# STM32.net
KiCad netlist of a schematic drawn in Altium Designer
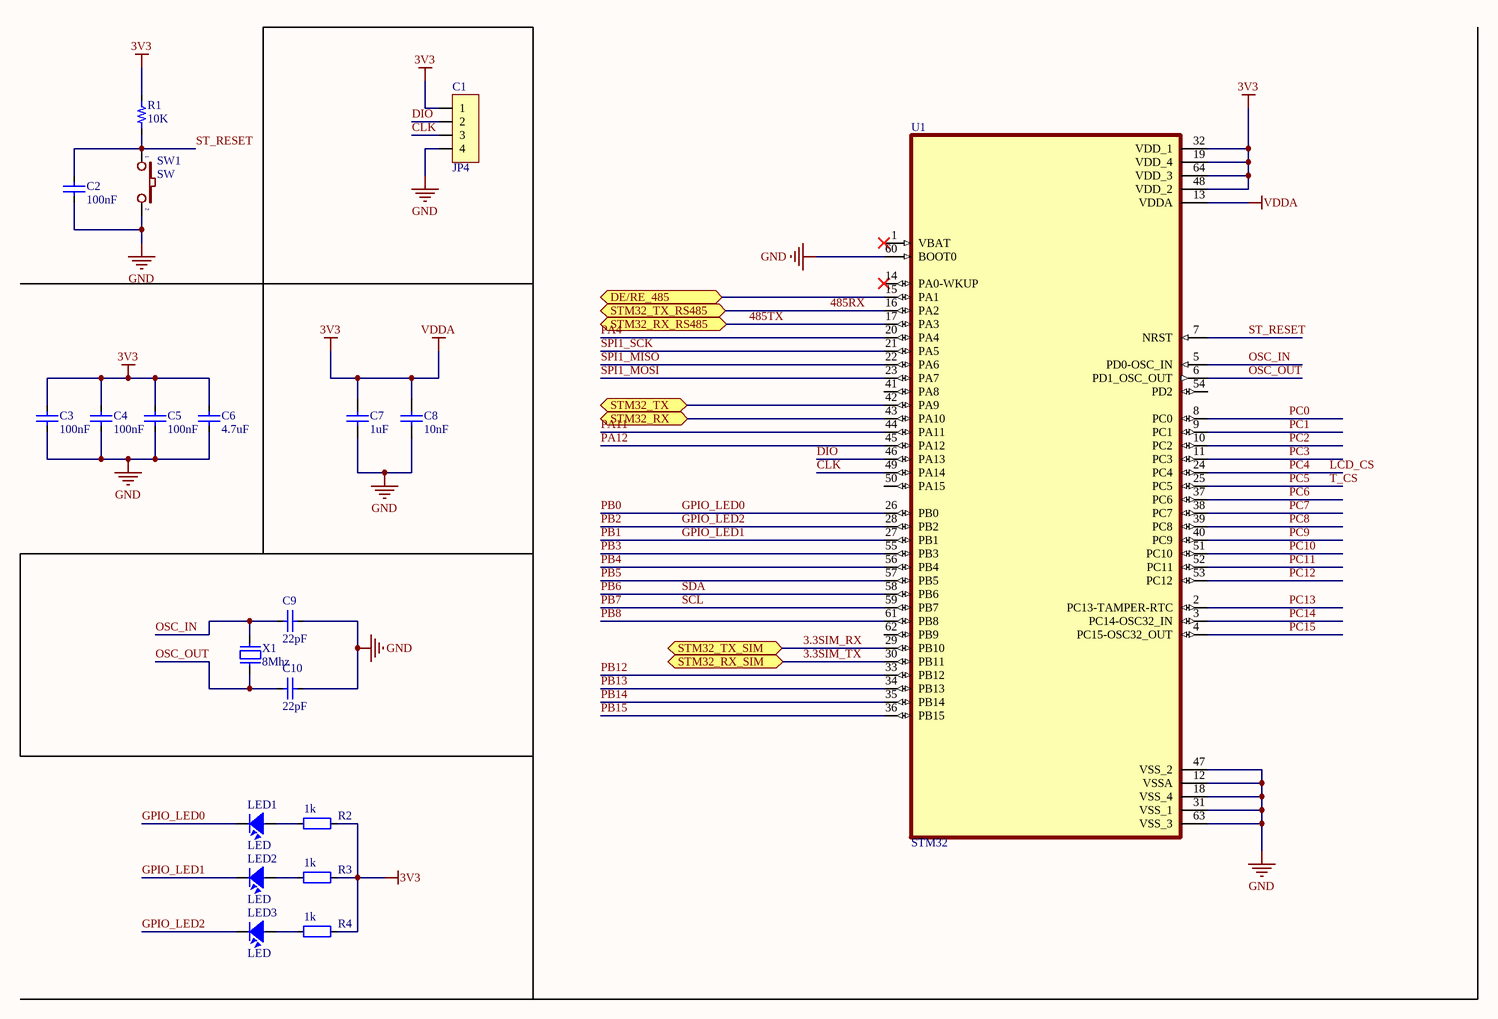
[diagram p0: STM32.SchDoc]

(export (version "E")
  (design (tool "Eeschema 10.0.6"))
  (components
    (comp (ref "C1")
      (value "JP4")
      (footprint "JP4-C1T")
      (description "WR-PHD 2.54 mm Angled Socket Header")
      (fields
        (field (name "MANUFACTURER") "Würth Elektronik eiSos GmbH")
        (field (name "PARTNO") "613004143121")
        (field (name "CREATED BY") "Karrer Zheng")
      )
      (libsource (lib "My-Library") (part "JP4"))
    )
    (comp (ref "C2")
      (value "100nF")
      (footprint "CAP_0805")
      (description "Capacitor")
      (fields (field (name "PUBLISHER") "Altium Limited"))
      (libsource (lib "My-Library") (part "CapSMD"))
    )
    (comp (ref "C3")
      (value "100nF")
      (footprint "CAP_0805")
      (description "Capacitor")
      (fields (field (name "PUBLISHER") "Altium Limited"))
      (libsource (lib "") (part "CapSMD_1"))
    )
    (comp (ref "C4")
      (value "100nF")
      (footprint "CAP_0805")
      (description "Capacitor")
      (fields (field (name "PUBLISHER") "Altium Limited"))
      (libsource (lib "") (part "CapSMD_1"))
    )
    (comp (ref "C5")
      (value "100nF")
      (footprint "CAP_0805")
      (description "Capacitor")
      (fields (field (name "PUBLISHER") "Altium Limited"))
      (libsource (lib "") (part "CapSMD_1"))
    )
    (comp (ref "C6")
      (value "4.7uF")
      (footprint "CAP_0805")
      (description "Capacitor")
      (fields (field (name "PUBLISHER") "Altium Limited"))
      (libsource (lib "") (part "CapSMD_1"))
    )
    (comp (ref "C7")
      (value "1uF")
      (footprint "CAP_0805")
      (description "Capacitor")
      (fields (field (name "PUBLISHER") "Altium Limited"))
      (libsource (lib "My Library") (part "CapSMD"))
    )
    (comp (ref "C8")
      (value "10nF")
      (footprint "CAP_0805")
      (description "Capacitor")
      (fields (field (name "PUBLISHER") "Altium Limited"))
      (libsource (lib "My Library") (part "CapSMD"))
    )
    (comp (ref "C9")
      (value "22pF")
      (footprint "CAP_0805")
      (description "Capacitor")
      (fields (field (name "PUBLISHER") "Altium Limited"))
      (libsource (lib "My-Library") (part "CapSMD"))
    )
    (comp (ref "C10")
      (value "22pF")
      (footprint "CAP_0805")
      (description "Capacitor")
      (fields (field (name "PUBLISHER") "Altium Limited"))
      (libsource (lib "My-Library") (part "CapSMD"))
    )
    (comp (ref "LED1")
      (value "LED")
      (footprint "LED-0805-Red")
      (description "LED Single colour Green and Red")
      (libsource (lib "My Library") (part "LED"))
    )
    (comp (ref "LED2")
      (value "LED")
      (footprint "LED-0805-Green")
      (description "LED Single colour Green and Red")
      (libsource (lib "My Library") (part "LED"))
    )
    (comp (ref "LED3")
      (value "LED")
      (footprint "LED-0805-Blue")
      (description "LED Single colour Green and Red")
      (libsource (lib "My Library") (part "LED"))
    )
    (comp (ref "R1")
      (value "10K")
      (footprint "RES-SMD-0101")
      (description "Resistor")
      (fields
        (field (name "MANUFACTURER") "Generic Components")
        (field (name "PUBLISHER") "Altium Hobart Technology Centre")
      )
      (libsource (lib "My-Library") (part "Resistor - SMD"))
    )
    (comp (ref "R2")
      (value "1k")
      (footprint "RES-SMD-0805")
      (description "Resistor")
      (fields
        (field (name "MANUFACTURER") "Generic Components")
        (field (name "PUBLISHER") "Altium Hobart Technology Centre")
      )
      (libsource (lib "My Library") (part "Resistor - SMD"))
    )
    (comp (ref "R3")
      (value "1k")
      (footprint "RES-SMD-0805")
      (description "Resistor")
      (fields
        (field (name "MANUFACTURER") "Generic Components")
        (field (name "PUBLISHER") "Altium Hobart Technology Centre")
      )
      (libsource (lib "My Library") (part "Resistor - SMD"))
    )
    (comp (ref "R4")
      (value "1k")
      (footprint "RES-SMD-0805")
      (description "Resistor")
      (fields
        (field (name "MANUFACTURER") "Generic Components")
        (field (name "PUBLISHER") "Altium Hobart Technology Centre")
      )
      (libsource (lib "My Library") (part "Resistor - SMD"))
    )
    (comp (ref "SW1")
      (value "SW")
      (footprint "SW2")
      (description "Switch button 2 pin")
      (libsource (lib "My-Library") (part "SW2"))
    )
    (comp (ref "U1")
      (value "STM32")
      (footprint "LQFP 64")
      (description "STM32 ARM-based 32-bit MCU 72MHz 256KB")
      (libsource (lib "Main") (part "STM32F103RCT6"))
    )
    (comp (ref "X1")
      (value "8Mhz")
      (footprint "XT2")
      (description "Crystal For all Crystal 2pin.")
      (libsource (lib "My-Library") (part "XT2"))
    )
  )
  (nets
    (net (code "1") (name "/3.3SIM_RX") (class "Default")
      (node (ref "U1") (pin "29") (pinfunction "PB10_29") (pintype "bidirectional"))
    )
    (net (code "2") (name "/3.3SIM_TX") (class "Default")
      (node (ref "U1") (pin "30") (pinfunction "PB11_30") (pintype "bidirectional"))
    )
    (net (code "3") (name "/485RX") (class "Default")
      (node (ref "U1") (pin "16") (pinfunction "PA2_16") (pintype "bidirectional"))
    )
    (net (code "4") (name "/485TX") (class "Default")
      (node (ref "U1") (pin "17") (pinfunction "PA3_17") (pintype "bidirectional"))
    )
    (net (code "5") (name "/CLK") (class "Default")
      (node (ref "C1") (pin "3") (pinfunction "3_3") (pintype "passive"))
      (node (ref "U1") (pin "49") (pinfunction "PA14_49") (pintype "bidirectional"))
    )
    (net (code "6") (name "/DE{slash}RE_485") (class "Default")
      (node (ref "U1") (pin "15") (pinfunction "PA1_15") (pintype "bidirectional"))
    )
    (net (code "7") (name "/DIO") (class "Default")
      (node (ref "C1") (pin "2") (pinfunction "2_2") (pintype "passive"))
      (node (ref "U1") (pin "46") (pinfunction "PA13_46") (pintype "bidirectional"))
    )
    (net (code "8") (name "/GPIO_LED0") (class "Default")
      (node (ref "LED1") (pin "2") (pinfunction "2_2") (pintype "passive"))
      (node (ref "U1") (pin "26") (pinfunction "PB0_26") (pintype "bidirectional"))
    )
    (net (code "9") (name "/GPIO_LED1") (class "Default")
      (node (ref "LED2") (pin "2") (pinfunction "2_2") (pintype "passive"))
      (node (ref "U1") (pin "27") (pinfunction "PB1_27") (pintype "bidirectional"))
    )
    (net (code "10") (name "/GPIO_LED2") (class "Default")
      (node (ref "LED3") (pin "2") (pinfunction "2_2") (pintype "passive"))
      (node (ref "U1") (pin "28") (pinfunction "PB2_28") (pintype "bidirectional"))
    )
    (net (code "11") (name "/LCD_CS") (class "Default")
      (node (ref "U1") (pin "24") (pinfunction "PC4_24") (pintype "bidirectional"))
    )
    (net (code "12") (name "/OSC_IN") (class "Default")
      (node (ref "C9") (pin "2") (pinfunction "2_2") (pintype "passive"))
      (node (ref "U1") (pin "5") (pinfunction "PD0-OSC_IN_5") (pintype "input"))
      (node (ref "X1") (pin "2") (pinfunction "2_2") (pintype "passive"))
    )
    (net (code "13") (name "/OSC_OUT") (class "Default")
      (node (ref "C10") (pin "2") (pinfunction "2_2") (pintype "passive"))
      (node (ref "U1") (pin "6") (pinfunction "PD1_OSC_OUT_6") (pintype "output"))
      (node (ref "X1") (pin "1") (pinfunction "1_1") (pintype "passive"))
    )
    (net (code "14") (name "/PA4") (class "Default")
      (node (ref "U1") (pin "20") (pinfunction "PA4_20") (pintype "bidirectional"))
    )
    (net (code "15") (name "/PA11") (class "Default")
      (node (ref "U1") (pin "44") (pinfunction "PA11_44") (pintype "bidirectional"))
    )
    (net (code "16") (name "/PA12") (class "Default")
      (node (ref "U1") (pin "45") (pinfunction "PA12_45") (pintype "bidirectional"))
    )
    (net (code "17") (name "/PB3") (class "Default")
      (node (ref "U1") (pin "55") (pinfunction "PB3_55") (pintype "bidirectional"))
    )
    (net (code "18") (name "/PB4") (class "Default")
      (node (ref "U1") (pin "56") (pinfunction "PB4_56") (pintype "bidirectional"))
    )
    (net (code "19") (name "/PB5") (class "Default")
      (node (ref "U1") (pin "57") (pinfunction "PB5_57") (pintype "bidirectional"))
    )
    (net (code "20") (name "/PB6") (class "Default")
      (node (ref "U1") (pin "58") (pinfunction "PB6_58") (pintype "bidirectional"))
    )
    (net (code "21") (name "/PB7") (class "Default")
      (node (ref "U1") (pin "59") (pinfunction "PB7_59") (pintype "bidirectional"))
    )
    (net (code "22") (name "/PB8") (class "Default")
      (node (ref "U1") (pin "61") (pinfunction "PB8_61") (pintype "bidirectional"))
    )
    (net (code "23") (name "/PB12") (class "Default")
      (node (ref "U1") (pin "33") (pinfunction "PB12_33") (pintype "bidirectional"))
    )
    (net (code "24") (name "/PB13") (class "Default")
      (node (ref "U1") (pin "34") (pinfunction "PB13_34") (pintype "bidirectional"))
    )
    (net (code "25") (name "/PB14") (class "Default")
      (node (ref "U1") (pin "35") (pinfunction "PB14_35") (pintype "bidirectional"))
    )
    (net (code "26") (name "/PB15") (class "Default")
      (node (ref "U1") (pin "36") (pinfunction "PB15_36") (pintype "bidirectional"))
    )
    (net (code "27") (name "/PC0") (class "Default")
      (node (ref "U1") (pin "8") (pinfunction "PC0_8") (pintype "bidirectional"))
    )
    (net (code "28") (name "/PC1") (class "Default")
      (node (ref "U1") (pin "9") (pinfunction "PC1_9") (pintype "bidirectional"))
    )
    (net (code "29") (name "/PC2") (class "Default")
      (node (ref "U1") (pin "10") (pinfunction "PC2_10") (pintype "bidirectional"))
    )
    (net (code "30") (name "/PC3") (class "Default")
      (node (ref "U1") (pin "11") (pinfunction "PC3_11") (pintype "bidirectional"))
    )
    (net (code "31") (name "/PC5") (class "Default")
      (node (ref "U1") (pin "25") (pinfunction "PC5_25") (pintype "bidirectional"))
    )
    (net (code "32") (name "/PC6") (class "Default")
      (node (ref "U1") (pin "37") (pinfunction "PC6_37") (pintype "bidirectional"))
    )
    (net (code "33") (name "/PC7") (class "Default")
      (node (ref "U1") (pin "38") (pinfunction "PC7_38") (pintype "bidirectional"))
    )
    (net (code "34") (name "/PC8") (class "Default")
      (node (ref "U1") (pin "39") (pinfunction "PC8_39") (pintype "bidirectional"))
    )
    (net (code "35") (name "/PC9") (class "Default")
      (node (ref "U1") (pin "40") (pinfunction "PC9_40") (pintype "bidirectional"))
    )
    (net (code "36") (name "/PC10") (class "Default")
      (node (ref "U1") (pin "51") (pinfunction "PC10_51") (pintype "bidirectional"))
    )
    (net (code "37") (name "/PC11") (class "Default")
      (node (ref "U1") (pin "52") (pinfunction "PC11_52") (pintype "bidirectional"))
    )
    (net (code "38") (name "/PC12") (class "Default")
      (node (ref "U1") (pin "53") (pinfunction "PC12_53") (pintype "bidirectional"))
    )
    (net (code "39") (name "/PC13") (class "Default")
      (node (ref "U1") (pin "2") (pinfunction "PC13-TAMPER-RTC_2") (pintype "bidirectional"))
    )
    (net (code "40") (name "/PC14") (class "Default")
      (node (ref "U1") (pin "3") (pinfunction "PC14-OSC32_IN_3") (pintype "bidirectional"))
    )
    (net (code "41") (name "/PC15") (class "Default")
      (node (ref "U1") (pin "4") (pinfunction "PC15-OSC32_OUT_4") (pintype "bidirectional"))
    )
    (net (code "42") (name "/SPI1_MISO") (class "Default")
      (node (ref "U1") (pin "22") (pinfunction "PA6_22") (pintype "bidirectional"))
    )
    (net (code "43") (name "/SPI1_MOSI") (class "Default")
      (node (ref "U1") (pin "23") (pinfunction "PA7_23") (pintype "bidirectional"))
    )
    (net (code "44") (name "/SPI1_SCK") (class "Default")
      (node (ref "U1") (pin "21") (pinfunction "PA5_21") (pintype "bidirectional"))
    )
    (net (code "45") (name "/STM32_RX") (class "Default")
      (node (ref "U1") (pin "43") (pinfunction "PA10_43") (pintype "bidirectional"))
    )
    (net (code "46") (name "/STM32_TX") (class "Default")
      (node (ref "U1") (pin "42") (pinfunction "PA9_42") (pintype "bidirectional"))
    )
    (net (code "47") (name "/ST_RESET") (class "Default")
      (node (ref "C2") (pin "1") (pinfunction "1_1") (pintype "passive"))
      (node (ref "R1") (pin "2") (pinfunction "2_2") (pintype "passive"))
      (node (ref "SW1") (pin "1") (pinfunction "1_1") (pintype "passive"))
      (node (ref "U1") (pin "7") (pinfunction "NRST_7") (pintype "input"))
    )
    (net (code "48") (name "3V3") (class "Default")
      (node (ref "C1") (pin "1") (pinfunction "1_1") (pintype "passive"))
      (node (ref "C3") (pin "2") (pinfunction "2_2") (pintype "passive"))
      (node (ref "C4") (pin "2") (pinfunction "2_2") (pintype "passive"))
      (node (ref "C5") (pin "2") (pinfunction "2_2") (pintype "passive"))
      (node (ref "C6") (pin "2") (pinfunction "2_2") (pintype "passive"))
      (node (ref "C7") (pin "2") (pinfunction "2_2") (pintype "passive"))
      (node (ref "C8") (pin "2") (pinfunction "2_2") (pintype "passive"))
      (node (ref "R1") (pin "1") (pinfunction "1_1") (pintype "passive"))
      (node (ref "R2") (pin "1") (pinfunction "1_1") (pintype "passive"))
      (node (ref "R3") (pin "1") (pinfunction "1_1") (pintype "passive"))
      (node (ref "R4") (pin "1") (pinfunction "1_1") (pintype "passive"))
      (node (ref "U1") (pin "13") (pinfunction "VDDA_13") (pintype "power_in"))
      (node (ref "U1") (pin "19") (pinfunction "VDD_4_19") (pintype "power_in"))
      (node (ref "U1") (pin "32") (pinfunction "VDD_1_32") (pintype "power_in"))
      (node (ref "U1") (pin "48") (pinfunction "VDD_2_48") (pintype "power_in"))
      (node (ref "U1") (pin "64") (pinfunction "VDD_3_64") (pintype "power_in"))
    )
    (net (code "49") (name "GND") (class "Default")
      (node (ref "C1") (pin "4") (pinfunction "4_4") (pintype "passive"))
      (node (ref "C10") (pin "1") (pinfunction "1_1") (pintype "passive"))
      (node (ref "C2") (pin "2") (pinfunction "2_2") (pintype "passive"))
      (node (ref "C3") (pin "1") (pinfunction "1_1") (pintype "passive"))
      (node (ref "C4") (pin "1") (pinfunction "1_1") (pintype "passive"))
      (node (ref "C5") (pin "1") (pinfunction "1_1") (pintype "passive"))
      (node (ref "C6") (pin "1") (pinfunction "1_1") (pintype "passive"))
      (node (ref "C7") (pin "1") (pinfunction "1_1") (pintype "passive"))
      (node (ref "C8") (pin "1") (pinfunction "1_1") (pintype "passive"))
      (node (ref "C9") (pin "1") (pinfunction "1_1") (pintype "passive"))
      (node (ref "SW1") (pin "2") (pinfunction "2_2") (pintype "passive"))
      (node (ref "U1") (pin "12") (pinfunction "VSSA_12") (pintype "power_in"))
      (node (ref "U1") (pin "18") (pinfunction "VSS_4_18") (pintype "power_in"))
      (node (ref "U1") (pin "31") (pinfunction "VSS_1_31") (pintype "power_in"))
      (node (ref "U1") (pin "47") (pinfunction "VSS_2_47") (pintype "power_in"))
      (node (ref "U1") (pin "60") (pinfunction "BOOT0_60") (pintype "input"))
      (node (ref "U1") (pin "63") (pinfunction "VSS_3_63") (pintype "power_in"))
    )
    (net (code "50") (name "Net-(LED1-Pad1)") (class "Default")
      (node (ref "LED1") (pin "1") (pinfunction "1_1") (pintype "passive"))
      (node (ref "R2") (pin "2") (pinfunction "2_2") (pintype "passive"))
    )
    (net (code "51") (name "Net-(LED2-Pad1)") (class "Default")
      (node (ref "LED2") (pin "1") (pinfunction "1_1") (pintype "passive"))
      (node (ref "R3") (pin "2") (pinfunction "2_2") (pintype "passive"))
    )
    (net (code "52") (name "Net-(LED3-Pad1)") (class "Default")
      (node (ref "LED3") (pin "1") (pinfunction "1_1") (pintype "passive"))
      (node (ref "R4") (pin "2") (pinfunction "2_2") (pintype "passive"))
    )
    (net (code "53") (name "unconnected-(U1-PA0-WKUP-Pad14)") (class "Default")
      (node (ref "U1") (pin "14") (pinfunction "PA0-WKUP_14") (pintype "bidirectional+no_connect"))
    )
    (net (code "54") (name "unconnected-(U1-PA8-Pad41)") (class "Default")
      (node (ref "U1") (pin "41") (pinfunction "PA8_41") (pintype "bidirectional"))
    )
    (net (code "55") (name "unconnected-(U1-PA15-Pad50)") (class "Default")
      (node (ref "U1") (pin "50") (pinfunction "PA15_50") (pintype "bidirectional"))
    )
    (net (code "56") (name "unconnected-(U1-PB9-Pad62)") (class "Default")
      (node (ref "U1") (pin "62") (pinfunction "PB9_62") (pintype "bidirectional"))
    )
    (net (code "57") (name "unconnected-(U1-PD2-Pad54)") (class "Default")
      (node (ref "U1") (pin "54") (pinfunction "PD2_54") (pintype "bidirectional"))
    )
    (net (code "58") (name "unconnected-(U1-VBAT-Pad1)") (class "Default")
      (node (ref "U1") (pin "1") (pinfunction "VBAT_1") (pintype "input+no_connect"))
    )
  )
)
